# iomodul2.net
KiCad netlist of a schematic drawn in EAGLE
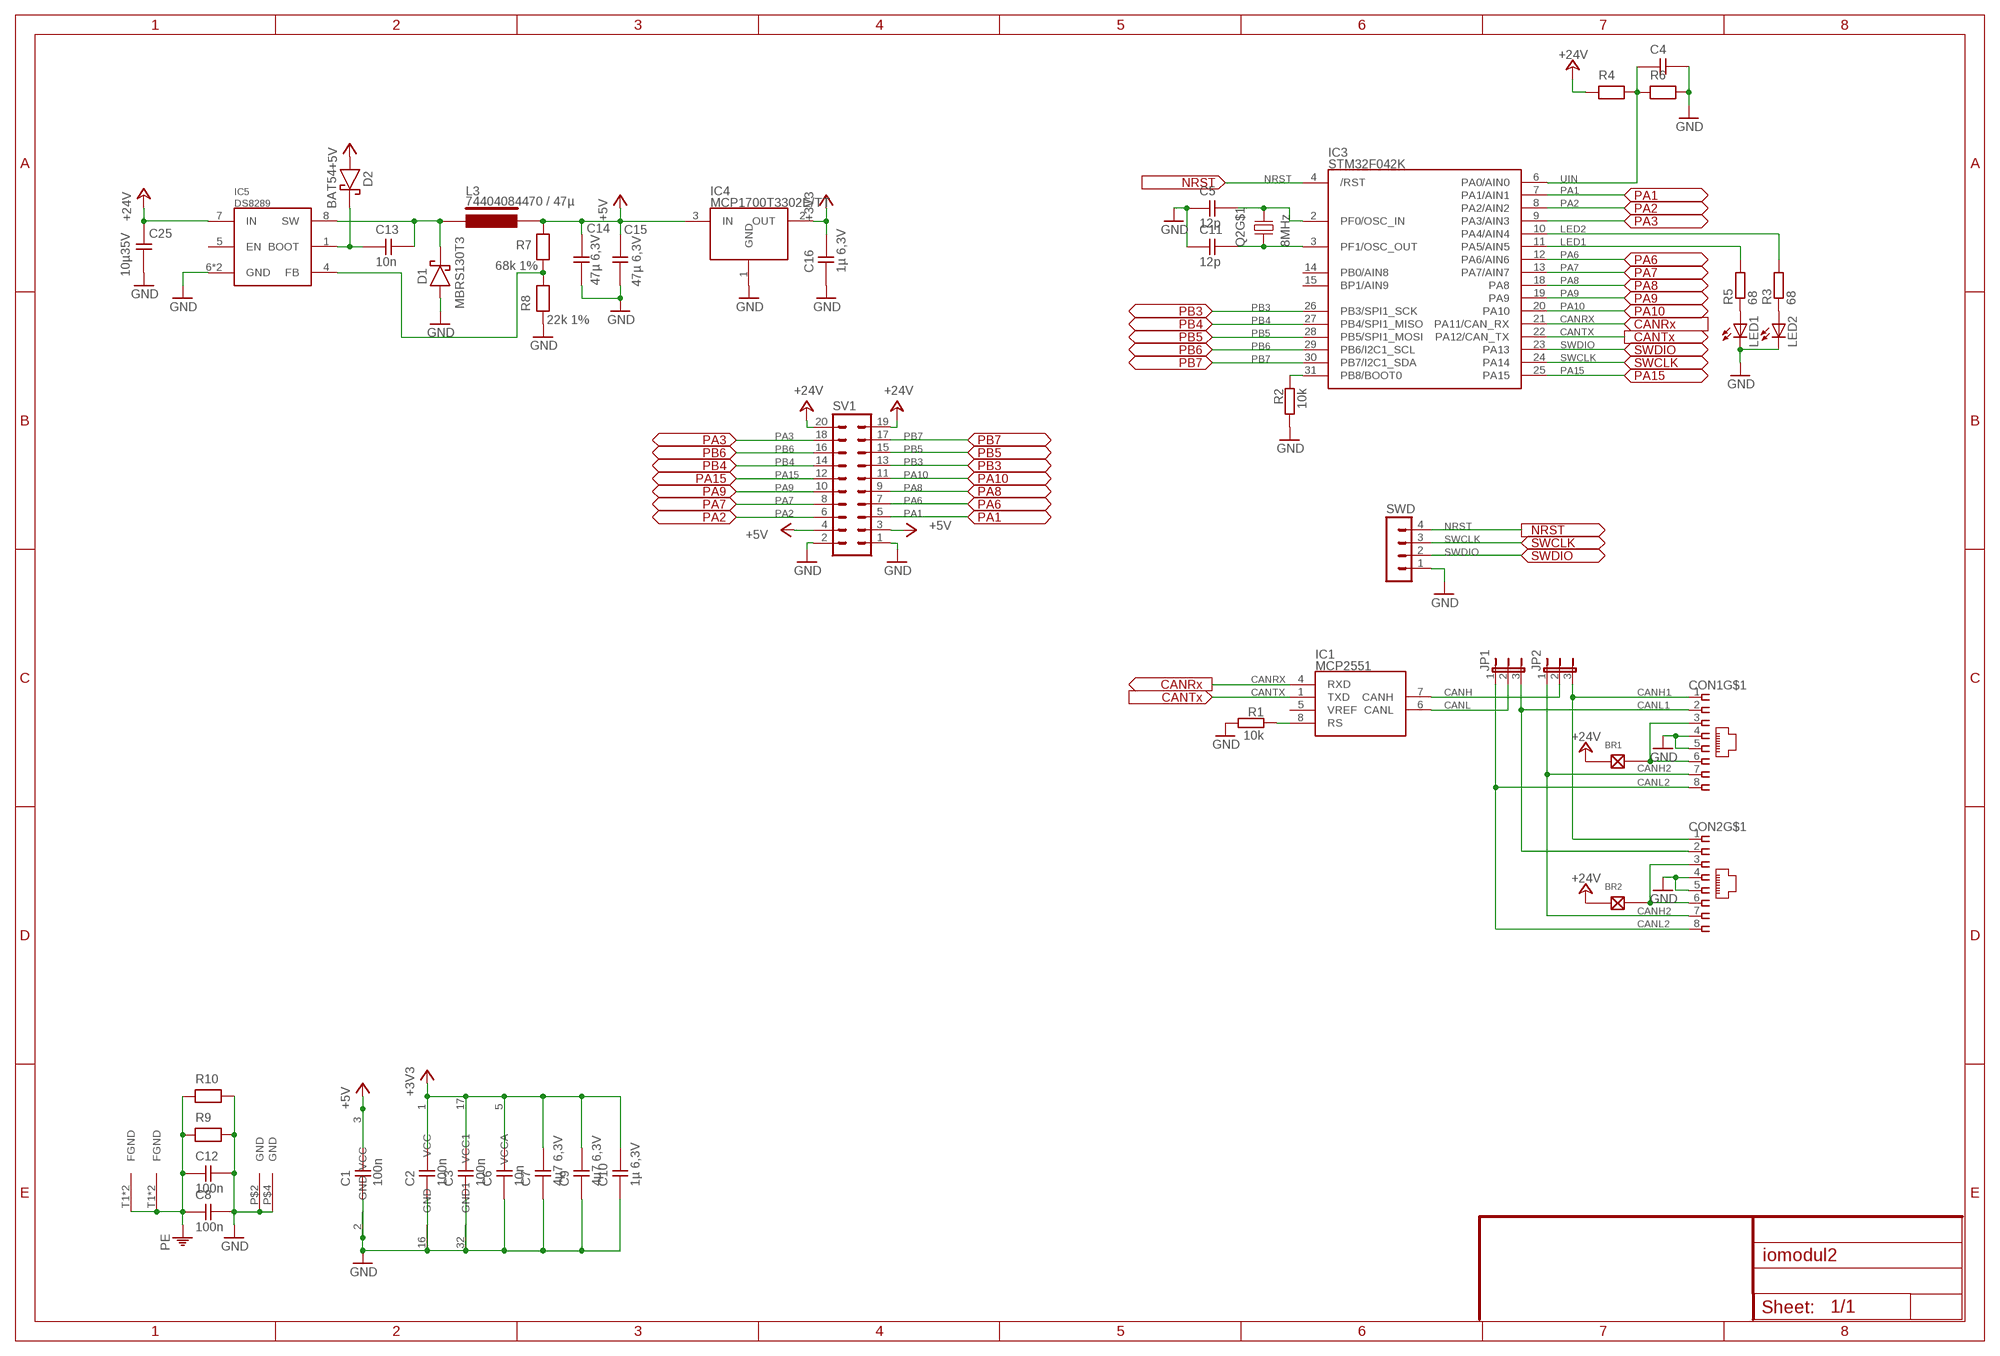
[diagram p0: schematic, sheet 1]

(export (version "E")
  (design (tool "Eeschema 10.0.6"))
  (components
    (comp (ref "BR1")
      (value "LÖTBRÜCKE-S")
      (footprint "eagle-import:LÖTBRÜCKE")
      (libsource (lib "eagle-import") (part "LÖTBRÜCKE-S"))
    )
    (comp (ref "BR2")
      (value "LÖTBRÜCKE-S")
      (footprint "eagle-import:LÖTBRÜCKE")
      (libsource (lib "eagle-import") (part "LÖTBRÜCKE-S"))
    )
    (comp (ref "C1")
      (value "100n")
      (footprint "eagle-import:0603REFLOW")
      (libsource (lib "eagle-import") (part "CAP0603R"))
    )
    (comp (ref "C2")
      (value "100n")
      (footprint "eagle-import:0603REFLOW")
      (libsource (lib "eagle-import") (part "CAP0603R"))
    )
    (comp (ref "C3")
      (value "100n")
      (footprint "eagle-import:0603REFLOW")
      (libsource (lib "eagle-import") (part "CAP0603R"))
    )
    (comp (ref "C4")
      (value "CAP0603R")
      (footprint "eagle-import:0603REFLOW")
      (libsource (lib "eagle-import") (part "CAP0603R"))
    )
    (comp (ref "C5")
      (value "12p")
      (footprint "eagle-import:0603REFLOW")
      (libsource (lib "eagle-import") (part "CAP0603R"))
    )
    (comp (ref "C6")
      (value "10n")
      (footprint "eagle-import:0603REFLOW")
      (libsource (lib "eagle-import") (part "CAP0603R"))
    )
    (comp (ref "C7")
      (value "4µ7 6,3V")
      (footprint "eagle-import:0603REFLOW")
      (libsource (lib "eagle-import") (part "CAP0603R"))
    )
    (comp (ref "C8")
      (value "100n")
      (footprint "eagle-import:0603REFLOW")
      (libsource (lib "eagle-import") (part "CAP0603R"))
    )
    (comp (ref "C9")
      (value "4µ7 6,3V")
      (footprint "eagle-import:0603REFLOW")
      (libsource (lib "eagle-import") (part "CAP0603R"))
    )
    (comp (ref "C10")
      (value "1µ 6,3V")
      (footprint "eagle-import:0603REFLOW")
      (libsource (lib "eagle-import") (part "CAP0603R"))
    )
    (comp (ref "C11")
      (value "12p")
      (footprint "eagle-import:0603REFLOW")
      (libsource (lib "eagle-import") (part "CAP0603R"))
    )
    (comp (ref "C12")
      (value "100n")
      (footprint "eagle-import:0603REFLOW")
      (libsource (lib "eagle-import") (part "CAP0603R"))
    )
    (comp (ref "C13")
      (value "10n")
      (footprint "eagle-import:0603REFLOW")
      (libsource (lib "eagle-import") (part "CAP0603R"))
    )
    (comp (ref "C14")
      (value "47µ 6,3V")
      (footprint "eagle-import:1210")
      (libsource (lib "eagle-import") (part "CAP1210"))
    )
    (comp (ref "C15")
      (value "47µ 6,3V")
      (footprint "eagle-import:1210")
      (libsource (lib "eagle-import") (part "CAP1210"))
    )
    (comp (ref "C16")
      (value "1µ 6,3V")
      (footprint "eagle-import:0603REFLOW")
      (libsource (lib "eagle-import") (part "CAP0603R"))
    )
    (comp (ref "C25")
      (value "10µ35V")
      (footprint "eagle-import:1206")
      (libsource (lib "eagle-import") (part "CAP1206"))
    )
    (comp (ref "CON1")
      (value "MEBP_8-8G")
      (footprint "eagle-import:MEBP")
      (libsource (lib "eagle-import") (part "MEBP_8-8G"))
    )
    (comp (ref "CON2")
      (value "MEBP_8-8G")
      (footprint "eagle-import:MEBP")
      (libsource (lib "eagle-import") (part "MEBP_8-8G"))
    )
    (comp (ref "D1")
      (value "MBRS130T3")
      (footprint "eagle-import:SMB")
      (libsource (lib "eagle-import") (part "MBRS130T3"))
    )
    (comp (ref "D2")
      (value "BAT54")
      (footprint "eagle-import:SOT23_32")
      (libsource (lib "eagle-import") (part "BAT54"))
    )
    (comp (ref "IC1")
      (value "MCP2551")
      (footprint "eagle-import:SO-8")
      (libsource (lib "eagle-import") (part "MCP2551"))
    )
    (comp (ref "IC3")
      (value "STM32F042K")
      (footprint "eagle-import:LQFP32")
      (libsource (lib "eagle-import") (part "STM32F042"))
    )
    (comp (ref "IC4")
      (value "MCP1700T3302E/TT")
      (footprint "eagle-import:SOT23")
      (libsource (lib "eagle-import") (part "MCP1700"))
    )
    (comp (ref "IC5")
      (value "DS8289")
      (footprint "eagle-import:SO8-POWERPAD")
      (libsource (lib "eagle-import") (part "DS8289"))
    )
    (comp (ref "JP1")
      (value "JP2E")
      (footprint "eagle-import:JP2")
      (libsource (lib "eagle-import") (part "JP2E"))
    )
    (comp (ref "JP2")
      (value "JP2E")
      (footprint "eagle-import:JP2")
      (libsource (lib "eagle-import") (part "JP2E"))
    )
    (comp (ref "L3")
      (value "74404084470 / 47µ")
      (footprint "eagle-import:WE-LQS")
      (libsource (lib "eagle-import") (part "WE-LQS"))
    )
    (comp (ref "LED1")
      (value "LEDCHIPLED_0603")
      (footprint "eagle-import:CHIPLED_0603")
      (libsource (lib "eagle-import") (part "LEDCHIPLED_0603"))
    )
    (comp (ref "LED2")
      (value "LEDCHIPLED_0603")
      (footprint "eagle-import:CHIPLED_0603")
      (libsource (lib "eagle-import") (part "LEDCHIPLED_0603"))
    )
    (comp (ref "Q2")
      (value "8MHz")
      (footprint "eagle-import:MT-CRYSTAL")
      (libsource (lib "eagle-import") (part "MT-CRYSTAL"))
    )
    (comp (ref "R1")
      (value "10k")
      (footprint "eagle-import:R0603")
      (libsource (lib "eagle-import") (part "R-EU_R0603"))
    )
    (comp (ref "R2")
      (value "10k")
      (footprint "eagle-import:R0603")
      (libsource (lib "eagle-import") (part "R-EU_R0603"))
    )
    (comp (ref "R3")
      (value "68")
      (footprint "eagle-import:R0603")
      (libsource (lib "eagle-import") (part "R-EU_R0603"))
    )
    (comp (ref "R4")
      (value "RES0603R")
      (footprint "eagle-import:0603REFLOW")
      (libsource (lib "eagle-import") (part "RES0603R"))
    )
    (comp (ref "R5")
      (value "68")
      (footprint "eagle-import:R0603")
      (libsource (lib "eagle-import") (part "R-EU_R0603"))
    )
    (comp (ref "R6")
      (value "RES0603R")
      (footprint "eagle-import:0603REFLOW")
      (libsource (lib "eagle-import") (part "RES0603R"))
    )
    (comp (ref "R7")
      (value "68k 1%")
      (footprint "eagle-import:0603REFLOW")
      (libsource (lib "eagle-import") (part "RES0603R"))
    )
    (comp (ref "R8")
      (value "22k 1%")
      (footprint "eagle-import:0603REFLOW")
      (libsource (lib "eagle-import") (part "RES0603R"))
    )
    (comp (ref "R9")
      (value "RES0603R")
      (footprint "eagle-import:0603REFLOW")
      (libsource (lib "eagle-import") (part "RES0603R"))
    )
    (comp (ref "R10")
      (value "RES0603R")
      (footprint "eagle-import:0603REFLOW")
      (libsource (lib "eagle-import") (part "RES0603R"))
    )
    (comp (ref "SV1")
      (value "MA10-2")
      (footprint "eagle-import:MA10-2")
      (libsource (lib "eagle-import") (part "MA10-2"))
    )
    (comp (ref "SWD")
      (value "MA04-1")
      (footprint "eagle-import:MA04-1")
      (libsource (lib "eagle-import") (part "MA04-1"))
    )
  )
  (nets
    (net (code "1") (name "+3V3") (class "Default")
      (node (ref "C10") (pin "2") (pinfunction "2_2") (pintype "passive"))
      (node (ref "C16") (pin "2") (pinfunction "2_2") (pintype "passive"))
      (node (ref "C2") (pin "2") (pinfunction "2_2") (pintype "passive"))
      (node (ref "C3") (pin "2") (pinfunction "2_2") (pintype "passive"))
      (node (ref "C6") (pin "2") (pinfunction "2_2") (pintype "passive"))
      (node (ref "C7") (pin "2") (pinfunction "2_2") (pintype "passive"))
      (node (ref "C9") (pin "2") (pinfunction "2_2") (pintype "passive"))
      (node (ref "IC3") (pin "1") (pinfunction "VCC_1") (pintype "power_in"))
      (node (ref "IC3") (pin "17") (pinfunction "VCC1_17") (pintype "power_in"))
      (node (ref "IC3") (pin "5") (pinfunction "VCCA_5") (pintype "power_in"))
      (node (ref "IC4") (pin "2") (pinfunction "OUT_2") (pintype "power_in"))
    )
    (net (code "2") (name "+5V") (class "Default")
      (node (ref "C1") (pin "2") (pinfunction "2_2") (pintype "passive"))
      (node (ref "C14") (pin "2") (pinfunction "2_2") (pintype "passive"))
      (node (ref "C15") (pin "2") (pinfunction "2_2") (pintype "passive"))
      (node (ref "D2") (pin "1") (pinfunction "A_1") (pintype "passive"))
      (node (ref "IC1") (pin "3") (pinfunction "VCC_3") (pintype "power_in"))
      (node (ref "IC4") (pin "3") (pinfunction "IN_3") (pintype "power_in"))
      (node (ref "L3") (pin "P$2") (pinfunction "P$2_P$2") (pintype "passive"))
      (node (ref "R7") (pin "2") (pinfunction "2_2") (pintype "passive"))
      (node (ref "SV1") (pin "3") (pinfunction "3_3") (pintype "passive"))
      (node (ref "SV1") (pin "4") (pinfunction "4_4") (pintype "passive"))
    )
    (net (code "3") (name "+24V") (class "Default")
      (node (ref "BR1") (pin "1") (pinfunction "1_1") (pintype "passive"))
      (node (ref "BR2") (pin "1") (pinfunction "1_1") (pintype "passive"))
      (node (ref "C25") (pin "2") (pinfunction "2_2") (pintype "passive"))
      (node (ref "IC5") (pin "7") (pinfunction "IN_7") (pintype "power_in"))
      (node (ref "R4") (pin "1") (pinfunction "1_1") (pintype "passive"))
      (node (ref "SV1") (pin "19") (pinfunction "19_19") (pintype "passive"))
      (node (ref "SV1") (pin "20") (pinfunction "20_20") (pintype "passive"))
    )
    (net (code "4") (name "/CANH") (class "Default")
      (node (ref "IC1") (pin "7") (pinfunction "CANH_7") (pintype "bidirectional"))
      (node (ref "JP2") (pin "2") (pinfunction "2_2") (pintype "passive"))
    )
    (net (code "5") (name "/CANH1") (class "Default")
      (node (ref "CON1") (pin "1") (pinfunction "1_1") (pintype "passive"))
      (node (ref "CON2") (pin "1") (pinfunction "1_1") (pintype "passive"))
      (node (ref "JP2") (pin "3") (pinfunction "3_3") (pintype "passive"))
    )
    (net (code "6") (name "/CANH2") (class "Default")
      (node (ref "CON1") (pin "7") (pinfunction "7_7") (pintype "passive"))
      (node (ref "CON2") (pin "7") (pinfunction "7_7") (pintype "passive"))
      (node (ref "JP2") (pin "1") (pinfunction "1_1") (pintype "passive"))
    )
    (net (code "7") (name "/CANL") (class "Default")
      (node (ref "IC1") (pin "6") (pinfunction "CANL_6") (pintype "bidirectional"))
      (node (ref "JP1") (pin "2") (pinfunction "2_2") (pintype "passive"))
    )
    (net (code "8") (name "/CANL1") (class "Default")
      (node (ref "CON1") (pin "2") (pinfunction "2_2") (pintype "passive"))
      (node (ref "CON2") (pin "2") (pinfunction "2_2") (pintype "passive"))
      (node (ref "JP1") (pin "3") (pinfunction "3_3") (pintype "passive"))
    )
    (net (code "9") (name "/CANL2") (class "Default")
      (node (ref "CON1") (pin "8") (pinfunction "8_8") (pintype "passive"))
      (node (ref "CON2") (pin "8") (pinfunction "8_8") (pintype "passive"))
      (node (ref "JP1") (pin "1") (pinfunction "1_1") (pintype "passive"))
    )
    (net (code "10") (name "/CANRX") (class "Default")
      (node (ref "IC1") (pin "4") (pinfunction "RXD_4") (pintype "bidirectional"))
      (node (ref "IC3") (pin "21") (pinfunction "PA11/CAN_RX_21") (pintype "bidirectional"))
    )
    (net (code "11") (name "/CANTX") (class "Default")
      (node (ref "IC1") (pin "1") (pinfunction "TXD_1") (pintype "bidirectional"))
      (node (ref "IC3") (pin "22") (pinfunction "PA12/CAN_TX_22") (pintype "bidirectional"))
    )
    (net (code "12") (name "/LED1") (class "Default")
      (node (ref "IC3") (pin "11") (pinfunction "PA5/AIN5_11") (pintype "bidirectional"))
      (node (ref "R5") (pin "2") (pinfunction "2_2") (pintype "passive"))
    )
    (net (code "13") (name "/LED2") (class "Default")
      (node (ref "IC3") (pin "10") (pinfunction "PA4/AIN4_10") (pintype "bidirectional"))
      (node (ref "R3") (pin "2") (pinfunction "2_2") (pintype "passive"))
    )
    (net (code "14") (name "/NRST") (class "Default")
      (node (ref "IC3") (pin "4") (pinfunction "/RST_4") (pintype "bidirectional"))
      (node (ref "SWD") (pin "4") (pinfunction "4_4") (pintype "passive"))
    )
    (net (code "15") (name "/PA1") (class "Default")
      (node (ref "IC3") (pin "7") (pinfunction "PA1/AIN1_7") (pintype "bidirectional"))
      (node (ref "SV1") (pin "5") (pinfunction "5_5") (pintype "passive"))
    )
    (net (code "16") (name "/PA2") (class "Default")
      (node (ref "IC3") (pin "8") (pinfunction "PA2/AIN2_8") (pintype "bidirectional"))
      (node (ref "SV1") (pin "6") (pinfunction "6_6") (pintype "passive"))
    )
    (net (code "17") (name "/PA3") (class "Default")
      (node (ref "IC3") (pin "9") (pinfunction "PA3/AIN3_9") (pintype "bidirectional"))
      (node (ref "SV1") (pin "18") (pinfunction "18_18") (pintype "passive"))
    )
    (net (code "18") (name "/PA6") (class "Default")
      (node (ref "IC3") (pin "12") (pinfunction "PA6/AIN6_12") (pintype "bidirectional"))
      (node (ref "SV1") (pin "7") (pinfunction "7_7") (pintype "passive"))
    )
    (net (code "19") (name "/PA7") (class "Default")
      (node (ref "IC3") (pin "13") (pinfunction "PA7/AIN7_13") (pintype "bidirectional"))
      (node (ref "SV1") (pin "8") (pinfunction "8_8") (pintype "passive"))
    )
    (net (code "20") (name "/PA8") (class "Default")
      (node (ref "IC3") (pin "18") (pinfunction "PA8_18") (pintype "bidirectional"))
      (node (ref "SV1") (pin "9") (pinfunction "9_9") (pintype "passive"))
    )
    (net (code "21") (name "/PA9") (class "Default")
      (node (ref "IC3") (pin "19") (pinfunction "PA9_19") (pintype "bidirectional"))
      (node (ref "SV1") (pin "10") (pinfunction "10_10") (pintype "passive"))
    )
    (net (code "22") (name "/PA10") (class "Default")
      (node (ref "IC3") (pin "20") (pinfunction "PA10_20") (pintype "bidirectional"))
      (node (ref "SV1") (pin "11") (pinfunction "11_11") (pintype "passive"))
    )
    (net (code "23") (name "/PA15") (class "Default")
      (node (ref "IC3") (pin "25") (pinfunction "PA15_25") (pintype "bidirectional"))
      (node (ref "SV1") (pin "12") (pinfunction "12_12") (pintype "passive"))
    )
    (net (code "24") (name "/PB3") (class "Default")
      (node (ref "IC3") (pin "26") (pinfunction "PB3/SPI1_SCK_26") (pintype "bidirectional"))
      (node (ref "SV1") (pin "13") (pinfunction "13_13") (pintype "passive"))
    )
    (net (code "25") (name "/PB4") (class "Default")
      (node (ref "IC3") (pin "27") (pinfunction "PB4/SPI1_MISO_27") (pintype "bidirectional"))
      (node (ref "SV1") (pin "14") (pinfunction "14_14") (pintype "passive"))
    )
    (net (code "26") (name "/PB5") (class "Default")
      (node (ref "IC3") (pin "28") (pinfunction "PB5/SPI1_MOSI_28") (pintype "bidirectional"))
      (node (ref "SV1") (pin "15") (pinfunction "15_15") (pintype "passive"))
    )
    (net (code "27") (name "/PB6") (class "Default")
      (node (ref "IC3") (pin "29") (pinfunction "PB6/I2C1_SCL_29") (pintype "bidirectional"))
      (node (ref "SV1") (pin "16") (pinfunction "16_16") (pintype "passive"))
    )
    (net (code "28") (name "/PB7") (class "Default")
      (node (ref "IC3") (pin "30") (pinfunction "PB7/I2C1_SDA_30") (pintype "bidirectional"))
      (node (ref "SV1") (pin "17") (pinfunction "17_17") (pintype "passive"))
    )
    (net (code "29") (name "/SWCLK") (class "Default")
      (node (ref "IC3") (pin "24") (pinfunction "PA14_24") (pintype "bidirectional"))
      (node (ref "SWD") (pin "3") (pinfunction "3_3") (pintype "passive"))
    )
    (net (code "30") (name "/SWDIO") (class "Default")
      (node (ref "IC3") (pin "23") (pinfunction "PA13_23") (pintype "bidirectional"))
      (node (ref "SWD") (pin "2") (pinfunction "2_2") (pintype "passive"))
    )
    (net (code "31") (name "/UIN") (class "Default")
      (node (ref "C4") (pin "1") (pinfunction "1_1") (pintype "passive"))
      (node (ref "IC3") (pin "6") (pinfunction "PA0/AIN0_6") (pintype "bidirectional"))
      (node (ref "R4") (pin "2") (pinfunction "2_2") (pintype "passive"))
      (node (ref "R6") (pin "1") (pinfunction "1_1") (pintype "passive"))
    )
    (net (code "32") (name "GND") (class "Default")
      (node (ref "C1") (pin "1") (pinfunction "1_1") (pintype "passive"))
      (node (ref "C10") (pin "1") (pinfunction "1_1") (pintype "passive"))
      (node (ref "C11") (pin "1") (pinfunction "1_1") (pintype "passive"))
      (node (ref "C12") (pin "2") (pinfunction "2_2") (pintype "passive"))
      (node (ref "C14") (pin "1") (pinfunction "1_1") (pintype "passive"))
      (node (ref "C15") (pin "1") (pinfunction "1_1") (pintype "passive"))
      (node (ref "C16") (pin "1") (pinfunction "1_1") (pintype "passive"))
      (node (ref "C2") (pin "1") (pinfunction "1_1") (pintype "passive"))
      (node (ref "C25") (pin "1") (pinfunction "1_1") (pintype "passive"))
      (node (ref "C3") (pin "1") (pinfunction "1_1") (pintype "passive"))
      (node (ref "C4") (pin "2") (pinfunction "2_2") (pintype "passive"))
      (node (ref "C5") (pin "1") (pinfunction "1_1") (pintype "passive"))
      (node (ref "C6") (pin "1") (pinfunction "1_1") (pintype "passive"))
      (node (ref "C7") (pin "1") (pinfunction "1_1") (pintype "passive"))
      (node (ref "C8") (pin "2") (pinfunction "2_2") (pintype "passive"))
      (node (ref "C9") (pin "1") (pinfunction "1_1") (pintype "passive"))
      (node (ref "CON1") (pin "4") (pinfunction "4_4") (pintype "passive"))
      (node (ref "CON1") (pin "5") (pinfunction "5_5") (pintype "passive"))
      (node (ref "CON2") (pin "4") (pinfunction "4_4") (pintype "passive"))
      (node (ref "CON2") (pin "5") (pinfunction "5_5") (pintype "passive"))
      (node (ref "D1") (pin "A") (pinfunction "A_A") (pintype "passive"))
      (node (ref "IC1") (pin "2") (pinfunction "GND_2") (pintype "power_in"))
      (node (ref "IC3") (pin "16") (pinfunction "GND_16") (pintype "power_in"))
      (node (ref "IC3") (pin "32") (pinfunction "GND1_32") (pintype "power_in"))
      (node (ref "IC4") (pin "1") (pinfunction "GND_1") (pintype "power_in"))
      (node (ref "IC5") (pin "6") (pinfunction "GND_6") (pintype "power_in"))
      (node (ref "IC5") (pin "TP") (pinfunction "GND_TP") (pintype "power_in"))
      (node (ref "LED1") (pin "C") (pinfunction "C_C") (pintype "passive"))
      (node (ref "LED2") (pin "C") (pinfunction "C_C") (pintype "passive"))
      (node (ref "Q2") (pin "P$2") (pinfunction "GND_P$2") (pintype "power_in"))
      (node (ref "Q2") (pin "P$4") (pinfunction "GND_P$4") (pintype "power_in"))
      (node (ref "R1") (pin "2") (pinfunction "2_2") (pintype "passive"))
      (node (ref "R10") (pin "2") (pinfunction "2_2") (pintype "passive"))
      (node (ref "R2") (pin "2") (pinfunction "2_2") (pintype "passive"))
      (node (ref "R6") (pin "2") (pinfunction "2_2") (pintype "passive"))
      (node (ref "R8") (pin "1") (pinfunction "1_1") (pintype "passive"))
      (node (ref "R9") (pin "2") (pinfunction "2_2") (pintype "passive"))
      (node (ref "SV1") (pin "1") (pinfunction "1_1") (pintype "passive"))
      (node (ref "SV1") (pin "2") (pinfunction "2_2") (pintype "passive"))
      (node (ref "SWD") (pin "1") (pinfunction "1_1") (pintype "passive"))
    )
    (net (code "33") (name "Net-(BR1-Pad2)") (class "Default")
      (node (ref "BR1") (pin "2") (pinfunction "2_2") (pintype "passive"))
      (node (ref "CON1") (pin "3") (pinfunction "3_3") (pintype "passive"))
      (node (ref "CON1") (pin "6") (pinfunction "6_6") (pintype "passive"))
    )
    (net (code "34") (name "Net-(BR2-Pad2)") (class "Default")
      (node (ref "BR2") (pin "2") (pinfunction "2_2") (pintype "passive"))
      (node (ref "CON2") (pin "3") (pinfunction "3_3") (pintype "passive"))
      (node (ref "CON2") (pin "6") (pinfunction "6_6") (pintype "passive"))
    )
    (net (code "35") (name "Net-(D2-K)") (class "Default")
      (node (ref "C13") (pin "1") (pinfunction "1_1") (pintype "passive"))
      (node (ref "D2") (pin "3") (pinfunction "K_3") (pintype "passive"))
      (node (ref "IC5") (pin "1") (pinfunction "BOOT_1") (pintype "power_in"))
    )
    (net (code "36") (name "Net-(IC1A-RS)") (class "Default")
      (node (ref "IC1") (pin "8") (pinfunction "RS_8") (pintype "bidirectional"))
      (node (ref "R1") (pin "1") (pinfunction "1_1") (pintype "passive"))
    )
    (net (code "37") (name "Net-(IC3A-PB8{slash}BOOT0)") (class "Default")
      (node (ref "IC3") (pin "31") (pinfunction "PB8/BOOT0_31") (pintype "bidirectional"))
      (node (ref "R2") (pin "1") (pinfunction "1_1") (pintype "passive"))
    )
    (net (code "38") (name "Net-(IC3A-PF0{slash}OSC_IN)") (class "Default")
      (node (ref "C5") (pin "2") (pinfunction "2_2") (pintype "passive"))
      (node (ref "IC3") (pin "2") (pinfunction "PF0/OSC_IN_2") (pintype "bidirectional"))
      (node (ref "Q2") (pin "P$3") (pinfunction "2_P$3") (pintype "passive"))
    )
    (net (code "39") (name "Net-(IC3A-PF1{slash}OSC_OUT)") (class "Default")
      (node (ref "C11") (pin "2") (pinfunction "2_2") (pintype "passive"))
      (node (ref "IC3") (pin "3") (pinfunction "PF1/OSC_OUT_3") (pintype "bidirectional"))
      (node (ref "Q2") (pin "P$1") (pinfunction "1_P$1") (pintype "passive"))
    )
    (net (code "40") (name "Net-(IC5-FB)") (class "Default")
      (node (ref "IC5") (pin "4") (pinfunction "FB_4") (pintype "input"))
      (node (ref "R7") (pin "1") (pinfunction "1_1") (pintype "passive"))
      (node (ref "R8") (pin "2") (pinfunction "2_2") (pintype "passive"))
    )
    (net (code "41") (name "Net-(IC5-SW)") (class "Default")
      (node (ref "C13") (pin "2") (pinfunction "2_2") (pintype "passive"))
      (node (ref "D1") (pin "K") (pinfunction "K_K") (pintype "passive"))
      (node (ref "IC5") (pin "8") (pinfunction "SW_8") (pintype "power_in"))
      (node (ref "L3") (pin "P$1") (pinfunction "P$1_P$1") (pintype "passive"))
    )
    (net (code "42") (name "Net-(LED1-PadA)") (class "Default")
      (node (ref "LED1") (pin "A") (pinfunction "A_A") (pintype "passive"))
      (node (ref "R5") (pin "1") (pinfunction "1_1") (pintype "passive"))
    )
    (net (code "43") (name "Net-(LED2-PadA)") (class "Default")
      (node (ref "LED2") (pin "A") (pinfunction "A_A") (pintype "passive"))
      (node (ref "R3") (pin "1") (pinfunction "1_1") (pintype "passive"))
    )
    (net (code "44") (name "PE") (class "Default")
      (node (ref "C12") (pin "1") (pinfunction "1_1") (pintype "passive"))
      (node (ref "C8") (pin "1") (pinfunction "1_1") (pintype "passive"))
      (node (ref "CON1") (pin "T1") (pinfunction "FGND_T1") (pintype "power_in"))
      (node (ref "CON1") (pin "T2") (pinfunction "FGND_T2") (pintype "power_in"))
      (node (ref "CON2") (pin "T1") (pinfunction "FGND_T1") (pintype "power_in"))
      (node (ref "CON2") (pin "T2") (pinfunction "FGND_T2") (pintype "power_in"))
      (node (ref "R10") (pin "1") (pinfunction "1_1") (pintype "passive"))
      (node (ref "R9") (pin "1") (pinfunction "1_1") (pintype "passive"))
    )
    (net (code "45") (name "unconnected-(IC1A-VREF-Pad5)") (class "Default")
      (node (ref "IC1") (pin "5") (pinfunction "VREF_5") (pintype "bidirectional"))
    )
    (net (code "46") (name "unconnected-(IC3A-BP1{slash}AIN9-Pad15)") (class "Default")
      (node (ref "IC3") (pin "15") (pinfunction "BP1/AIN9_15") (pintype "bidirectional"))
    )
    (net (code "47") (name "unconnected-(IC3A-PB0{slash}AIN8-Pad14)") (class "Default")
      (node (ref "IC3") (pin "14") (pinfunction "PB0/AIN8_14") (pintype "bidirectional"))
    )
    (net (code "48") (name "unconnected-(IC5-EN-Pad5)") (class "Default")
      (node (ref "IC5") (pin "5") (pinfunction "EN_5") (pintype "input"))
    )
  )
)
